# adapter.net
KiCad netlist of a schematic drawn in Altium Designer
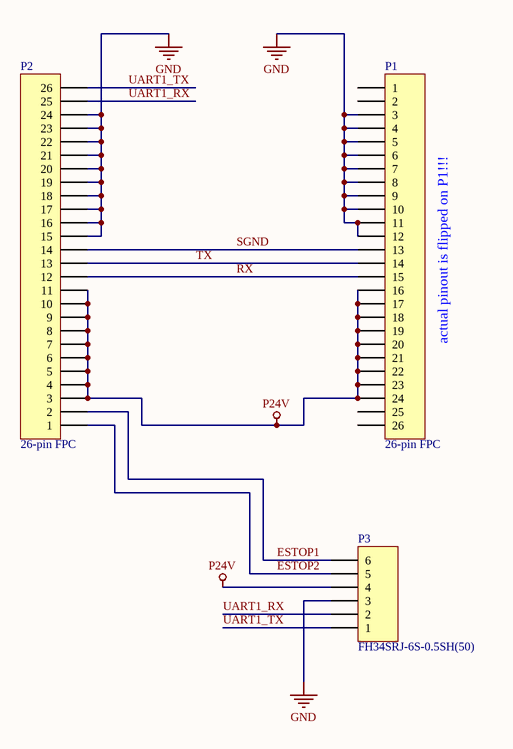
[diagram p0: adapter.SchDoc]

(export (version "E")
  (design (tool "Eeschema 10.0.6"))
  (components
    (comp (ref "P1")
      (value "26-pin FPC")
      (footprint "HRS_FH34SRJ-26S-0.5SH(50)")
      (description "26 Pin FPC header")
      (fields (field (name "MPN") "FH34SRJ-26S-0.5SH(99)"))
      (libsource (lib "commonsch-new") (part "FPC-26"))
    )
    (comp (ref "P2")
      (value "26-pin FPC")
      (footprint "HRS_FH34SRJ-26S-0.5SH(50)")
      (description "26 Pin FPC header")
      (fields (field (name "MPN") "FH34SRJ-26S-0.5SH(99)"))
      (libsource (lib "") (part "FPC-26_1"))
    )
    (comp (ref "P3")
      (value "FH34SRJ-6S-0.5SH(50)")
      (footprint "HRS_FH34SRJ-6S-0.5SH(50)")
      (description "Header, 6-Pin")
      (fields (field (name "PUBLISHER") "Altium Limited"))
      (libsource (lib "Miscellaneous Connectors") (part "Header 6"))
    )
  )
  (nets
    (net (code "1") (name "/ESTOP1") (class "Default")
      (node (ref "P2") (pin "2") (pinfunction "2_2") (pintype "passive"))
      (node (ref "P3") (pin "6") (pinfunction "6_6") (pintype "passive"))
    )
    (net (code "2") (name "/ESTOP2") (class "Default")
      (node (ref "P2") (pin "1") (pinfunction "1_1") (pintype "passive"))
      (node (ref "P3") (pin "5") (pinfunction "5_5") (pintype "passive"))
    )
    (net (code "3") (name "/RX") (class "Default")
      (node (ref "P1") (pin "15") (pinfunction "15_15") (pintype "passive"))
      (node (ref "P2") (pin "12") (pinfunction "12_12") (pintype "passive"))
    )
    (net (code "4") (name "/SGND") (class "Default")
      (node (ref "P1") (pin "13") (pinfunction "13_13") (pintype "passive"))
      (node (ref "P2") (pin "14") (pinfunction "14_14") (pintype "passive"))
    )
    (net (code "5") (name "/TX") (class "Default")
      (node (ref "P1") (pin "14") (pinfunction "14_14") (pintype "passive"))
      (node (ref "P2") (pin "13") (pinfunction "13_13") (pintype "passive"))
    )
    (net (code "6") (name "/UART1_RX") (class "Default")
      (node (ref "P2") (pin "25") (pinfunction "25_25") (pintype "passive"))
      (node (ref "P3") (pin "2") (pinfunction "2_2") (pintype "passive"))
    )
    (net (code "7") (name "/UART1_TX") (class "Default")
      (node (ref "P2") (pin "26") (pinfunction "26_26") (pintype "passive"))
      (node (ref "P3") (pin "1") (pinfunction "1_1") (pintype "passive"))
    )
    (net (code "8") (name "GND") (class "Default")
      (node (ref "P1") (pin "10") (pinfunction "10_10") (pintype "passive"))
      (node (ref "P1") (pin "11") (pinfunction "11_11") (pintype "passive"))
      (node (ref "P1") (pin "12") (pinfunction "12_12") (pintype "passive"))
      (node (ref "P1") (pin "3") (pinfunction "3_3") (pintype "passive"))
      (node (ref "P1") (pin "4") (pinfunction "4_4") (pintype "passive"))
      (node (ref "P1") (pin "5") (pinfunction "5_5") (pintype "passive"))
      (node (ref "P1") (pin "6") (pinfunction "6_6") (pintype "passive"))
      (node (ref "P1") (pin "7") (pinfunction "7_7") (pintype "passive"))
      (node (ref "P1") (pin "8") (pinfunction "8_8") (pintype "passive"))
      (node (ref "P1") (pin "9") (pinfunction "9_9") (pintype "passive"))
      (node (ref "P2") (pin "15") (pinfunction "15_15") (pintype "passive"))
      (node (ref "P2") (pin "16") (pinfunction "16_16") (pintype "passive"))
      (node (ref "P2") (pin "17") (pinfunction "17_17") (pintype "passive"))
      (node (ref "P2") (pin "18") (pinfunction "18_18") (pintype "passive"))
      (node (ref "P2") (pin "19") (pinfunction "19_19") (pintype "passive"))
      (node (ref "P2") (pin "20") (pinfunction "20_20") (pintype "passive"))
      (node (ref "P2") (pin "21") (pinfunction "21_21") (pintype "passive"))
      (node (ref "P2") (pin "22") (pinfunction "22_22") (pintype "passive"))
      (node (ref "P2") (pin "23") (pinfunction "23_23") (pintype "passive"))
      (node (ref "P2") (pin "24") (pinfunction "24_24") (pintype "passive"))
      (node (ref "P3") (pin "3") (pinfunction "3_3") (pintype "passive"))
    )
    (net (code "9") (name "P24V") (class "Default")
      (node (ref "P1") (pin "16") (pinfunction "16_16") (pintype "passive"))
      (node (ref "P1") (pin "17") (pinfunction "17_17") (pintype "passive"))
      (node (ref "P1") (pin "18") (pinfunction "18_18") (pintype "passive"))
      (node (ref "P1") (pin "19") (pinfunction "19_19") (pintype "passive"))
      (node (ref "P1") (pin "20") (pinfunction "20_20") (pintype "passive"))
      (node (ref "P1") (pin "21") (pinfunction "21_21") (pintype "passive"))
      (node (ref "P1") (pin "22") (pinfunction "22_22") (pintype "passive"))
      (node (ref "P1") (pin "23") (pinfunction "23_23") (pintype "passive"))
      (node (ref "P1") (pin "24") (pinfunction "24_24") (pintype "passive"))
      (node (ref "P2") (pin "10") (pinfunction "10_10") (pintype "passive"))
      (node (ref "P2") (pin "11") (pinfunction "11_11") (pintype "passive"))
      (node (ref "P2") (pin "3") (pinfunction "3_3") (pintype "passive"))
      (node (ref "P2") (pin "4") (pinfunction "4_4") (pintype "passive"))
      (node (ref "P2") (pin "5") (pinfunction "5_5") (pintype "passive"))
      (node (ref "P2") (pin "6") (pinfunction "6_6") (pintype "passive"))
      (node (ref "P2") (pin "7") (pinfunction "7_7") (pintype "passive"))
      (node (ref "P2") (pin "8") (pinfunction "8_8") (pintype "passive"))
      (node (ref "P2") (pin "9") (pinfunction "9_9") (pintype "passive"))
      (node (ref "P3") (pin "4") (pinfunction "4_4") (pintype "passive"))
    )
    (net (code "10") (name "unconnected-(P1-Pad1)") (class "Default")
      (node (ref "P1") (pin "1") (pinfunction "1_1") (pintype "passive"))
    )
    (net (code "11") (name "unconnected-(P1-Pad2)") (class "Default")
      (node (ref "P1") (pin "2") (pinfunction "2_2") (pintype "passive"))
    )
    (net (code "12") (name "unconnected-(P1-Pad25)") (class "Default")
      (node (ref "P1") (pin "25") (pinfunction "25_25") (pintype "passive"))
    )
    (net (code "13") (name "unconnected-(P1-Pad26)") (class "Default")
      (node (ref "P1") (pin "26") (pinfunction "26_26") (pintype "passive"))
    )
  )
)
